# ioboard2.net
KiCad netlist of a schematic drawn in EAGLE
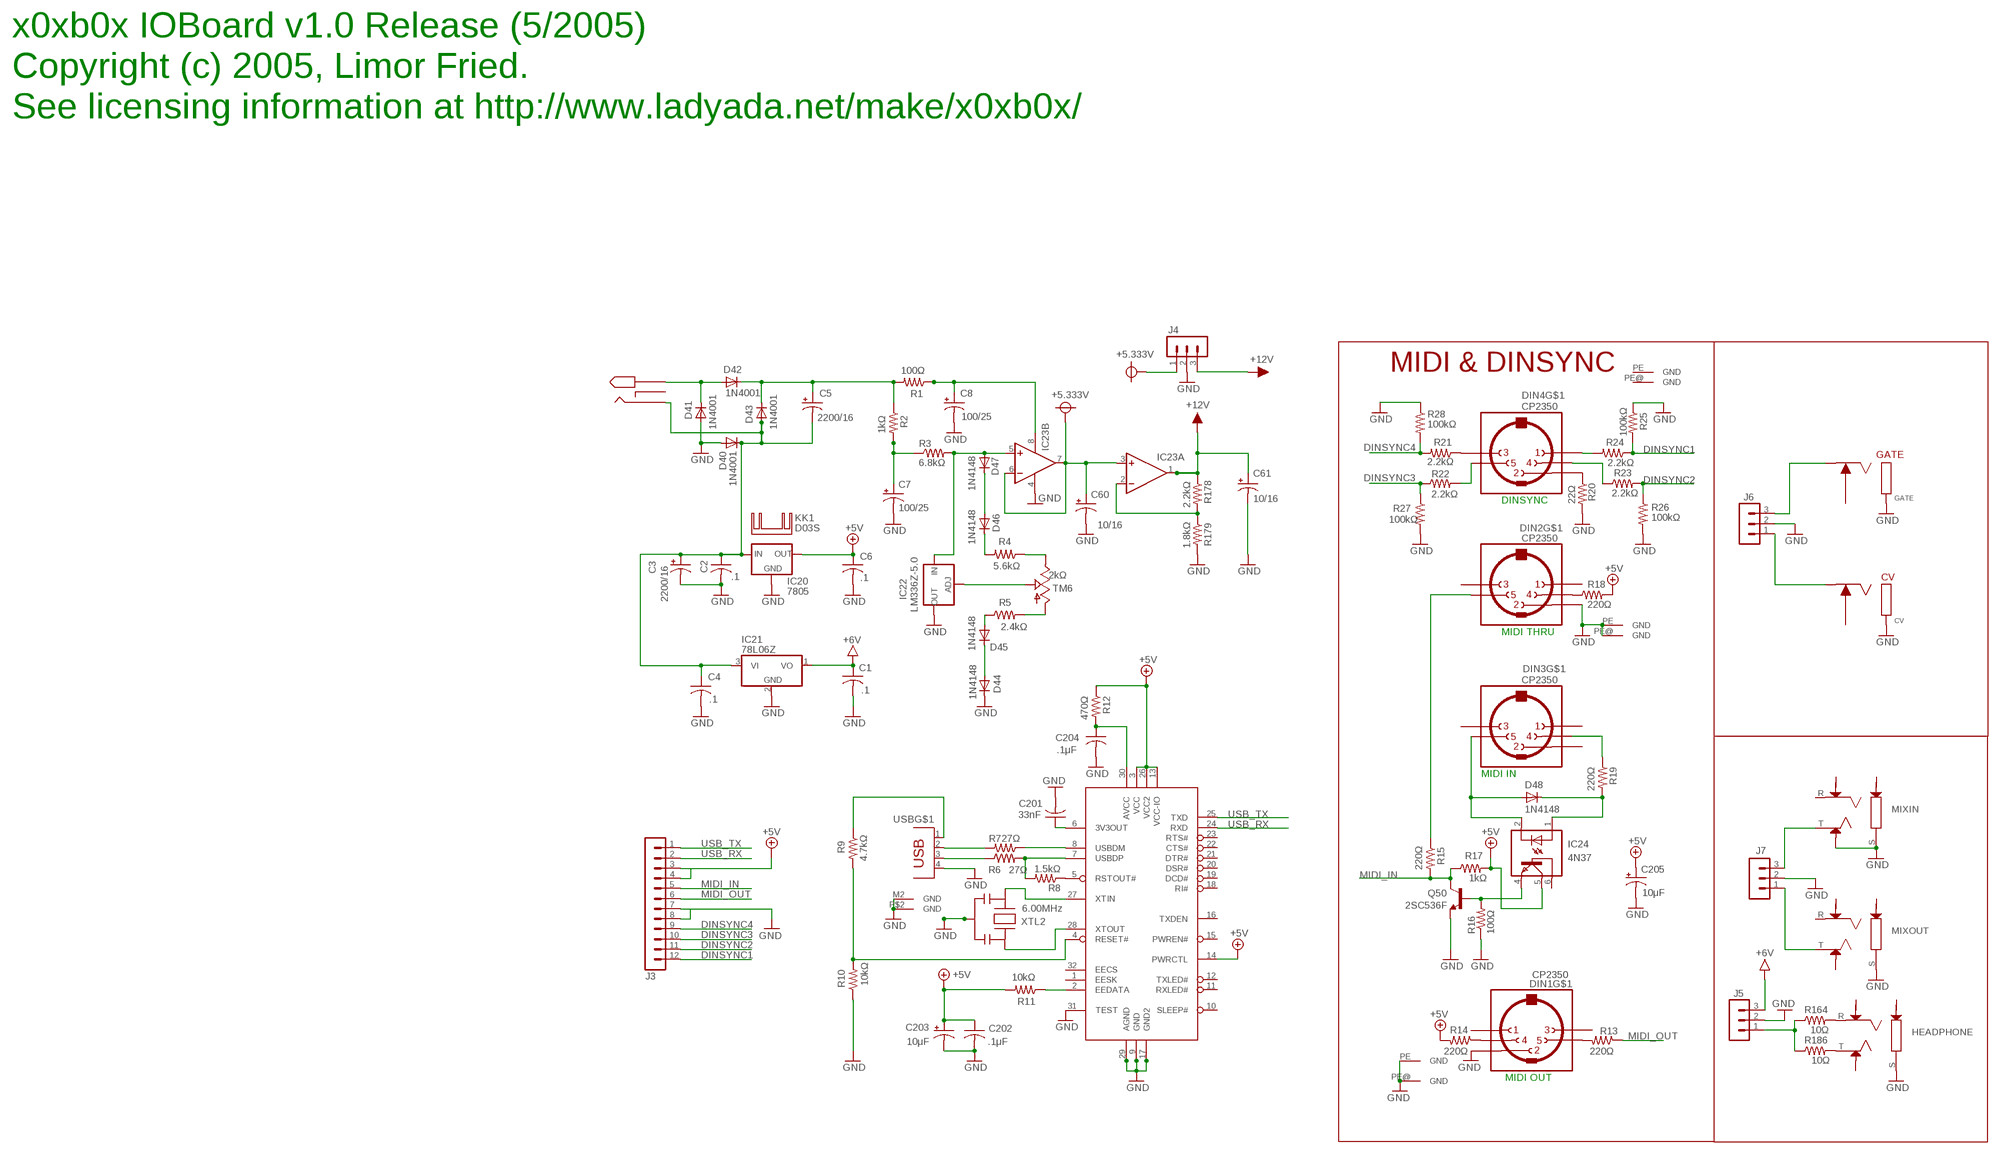
[diagram p0: schematic, sheet 1]

(export (version "E")
  (design (tool "Eeschema 10.0.6"))
  (components
    (comp (ref "C1")
      (value ".1")
      (footprint "eagle-import:C050H075X075")
      (libsource (lib "eagle-import") (part "C-US050H075X075"))
    )
    (comp (ref "C2")
      (value ".1")
      (footprint "eagle-import:C050H075X075")
      (libsource (lib "eagle-import") (part "C-US050H075X075"))
    )
    (comp (ref "C3")
      (value "2200/16")
      (footprint "eagle-import:E5-13")
      (libsource (lib "eagle-import") (part "CPOL-USE5-13"))
    )
    (comp (ref "C4")
      (value ".1")
      (footprint "eagle-import:C050H075X075")
      (libsource (lib "eagle-import") (part "C-US050H075X075"))
    )
    (comp (ref "C5")
      (value "2200/16")
      (footprint "eagle-import:E5-13")
      (libsource (lib "eagle-import") (part "CPOL-USE5-13"))
    )
    (comp (ref "C6")
      (value ".1")
      (footprint "eagle-import:C050H075X075")
      (libsource (lib "eagle-import") (part "C-US050H075X075"))
    )
    (comp (ref "C7")
      (value "100/25")
      (footprint "eagle-import:E5-6")
      (libsource (lib "eagle-import") (part "CPOL-USE5-6"))
    )
    (comp (ref "C8")
      (value "100/25")
      (footprint "eagle-import:E5-6")
      (libsource (lib "eagle-import") (part "CPOL-USE5-6"))
    )
    (comp (ref "C60")
      (value "10/16")
      (footprint "eagle-import:E5-6")
      (libsource (lib "eagle-import") (part "CPOL-USE5-6"))
    )
    (comp (ref "C61")
      (value "10/16")
      (footprint "eagle-import:E5-6")
      (libsource (lib "eagle-import") (part "CPOL-USE5-6"))
    )
    (comp (ref "C201")
      (value "33nF")
      (footprint "eagle-import:C050-025X075")
      (libsource (lib "eagle-import") (part "C-US050-025X075"))
    )
    (comp (ref "C202")
      (value ".1μF")
      (footprint "eagle-import:C050H075X075")
      (libsource (lib "eagle-import") (part "C-US050H075X075"))
    )
    (comp (ref "C203")
      (value "10μF")
      (footprint "eagle-import:E5-6")
      (libsource (lib "eagle-import") (part "CPOL-USE5-6"))
    )
    (comp (ref "C204")
      (value ".1μF")
      (footprint "eagle-import:C050H075X075")
      (libsource (lib "eagle-import") (part "C-US050H075X075"))
    )
    (comp (ref "C205")
      (value "10μF")
      (footprint "eagle-import:E5-6")
      (libsource (lib "eagle-import") (part "CPOL-USE5-6"))
    )
    (comp (ref "CV")
      (value "MONO_CC")
      (footprint "eagle-import:CP-3502")
      (libsource (lib "eagle-import") (part "MONO_CC"))
    )
    (comp (ref "D40")
      (value "1N4001")
      (footprint "eagle-import:DO41-10")
      (libsource (lib "eagle-import") (part "1N4004"))
    )
    (comp (ref "D41")
      (value "1N4001")
      (footprint "eagle-import:DO41-10")
      (libsource (lib "eagle-import") (part "1N4004"))
    )
    (comp (ref "D42")
      (value "1N4001")
      (footprint "eagle-import:DO41-10")
      (libsource (lib "eagle-import") (part "1N4004"))
    )
    (comp (ref "D43")
      (value "1N4001")
      (footprint "eagle-import:DO41-10")
      (libsource (lib "eagle-import") (part "1N4004"))
    )
    (comp (ref "D44")
      (value "1N4148")
      (footprint "eagle-import:DO35-10")
      (libsource (lib "eagle-import") (part "1N4148"))
    )
    (comp (ref "D45")
      (value "1N4148")
      (footprint "eagle-import:DO35-10")
      (libsource (lib "eagle-import") (part "1N4148"))
    )
    (comp (ref "D46")
      (value "1N4148")
      (footprint "eagle-import:DO35-10")
      (libsource (lib "eagle-import") (part "1N4148"))
    )
    (comp (ref "D47")
      (value "1N4148")
      (footprint "eagle-import:DO35-10")
      (libsource (lib "eagle-import") (part "1N4148"))
    )
    (comp (ref "D48")
      (value "1N4148")
      (footprint "eagle-import:DO35-10")
      (libsource (lib "eagle-import") (part "1N4148"))
    )
    (comp (ref "DIN1")
      (value "CP2350")
      (footprint "eagle-import:CP-2350")
      (libsource (lib "eagle-import") (part "CP2350"))
    )
    (comp (ref "DIN2")
      (value "CP2350")
      (footprint "eagle-import:CP-2350")
      (libsource (lib "eagle-import") (part "CP2350"))
    )
    (comp (ref "DIN3")
      (value "CP2350")
      (footprint "eagle-import:CP-2350")
      (libsource (lib "eagle-import") (part "CP2350"))
    )
    (comp (ref "DIN4")
      (value "CP2350")
      (footprint "eagle-import:CP-2350")
      (libsource (lib "eagle-import") (part "CP2350"))
    )
    (comp (ref "GATE")
      (value "MONO_CC")
      (footprint "eagle-import:CP-3502")
      (libsource (lib "eagle-import") (part "MONO_CC"))
    )
    (comp (ref "HEADPHONE")
      (value "NEUTRIX_STEREO")
      (footprint "eagle-import:REAN_1_4STERO")
      (libsource (lib "eagle-import") (part "NEUTRIX_STEREO"))
    )
    (comp (ref "IC20")
      (value "7805")
      (footprint "eagle-import:78XXS")
      (libsource (lib "eagle-import") (part "78XXS"))
    )
    (comp (ref "IC21")
      (value "78L06Z")
      (footprint "eagle-import:TO92")
      (libsource (lib "eagle-import") (part "78ZL05"))
    )
    (comp (ref "IC22")
      (value "LM336Z-5.0")
      (footprint "eagle-import:2SC536F")
      (libsource (lib "eagle-import") (part "LM337LX0X"))
    )
    (comp (ref "IC23")
      (value "AN6562N")
      (footprint "eagle-import:DIL08")
      (libsource (lib "eagle-import") (part "AN6562N"))
    )
    (comp (ref "IC24")
      (value "4N37")
      (footprint "eagle-import:DIL06")
      (libsource (lib "eagle-import") (part "4N37"))
    )
    (comp (ref "IC25")
      (value "FT232")
      (footprint "eagle-import:SQFP-S-7X7-32")
      (libsource (lib "eagle-import") (part "FT232"))
    )
    (comp (ref "J3")
      (value "MA12-1")
      (footprint "eagle-import:MA12-1")
      (libsource (lib "eagle-import") (part "MA12-1"))
    )
    (comp (ref "J4")
      (value "MA03-1")
      (footprint "eagle-import:MA03-1")
      (libsource (lib "eagle-import") (part "MA03-1"))
    )
    (comp (ref "J5")
      (value "MA03-1")
      (footprint "eagle-import:MA03-1")
      (libsource (lib "eagle-import") (part "MA03-1"))
    )
    (comp (ref "J6")
      (value "MA03-1")
      (footprint "eagle-import:MA03-1")
      (libsource (lib "eagle-import") (part "MA03-1"))
    )
    (comp (ref "J7")
      (value "MA03-1")
      (footprint "eagle-import:MA03-1")
      (libsource (lib "eagle-import") (part "MA03-1"))
    )
    (comp (ref "KK1")
      (value "D03S")
      (footprint "eagle-import:D03S")
      (libsource (lib "eagle-import") (part "D03S"))
    )
    (comp (ref "MIXIN")
      (value "NEUTRIX_STEREO")
      (footprint "eagle-import:REAN_1_4STERO")
      (libsource (lib "eagle-import") (part "NEUTRIX_STEREO"))
    )
    (comp (ref "MIXOUT")
      (value "NEUTRIX_STEREO")
      (footprint "eagle-import:REAN_1_4STERO")
      (libsource (lib "eagle-import") (part "NEUTRIX_STEREO"))
    )
    (comp (ref "POWER")
      (value "2.1MMJACK")
      (footprint "eagle-import:PJ-102A")
      (libsource (lib "eagle-import") (part "2.1MMJACK"))
    )
    (comp (ref "Q50")
      (value "2SC536F")
      (footprint "eagle-import:2SC536F")
      (libsource (lib "eagle-import") (part "2SC536F"))
    )
    (comp (ref "R1")
      (value "100Ω")
      (footprint "eagle-import:0207_5V")
      (libsource (lib "eagle-import") (part "R-US_0207/5V"))
    )
    (comp (ref "R2")
      (value "1kΩ")
      (footprint "eagle-import:0207_5V")
      (libsource (lib "eagle-import") (part "R-US_0207/5V"))
    )
    (comp (ref "R3")
      (value "6.8kΩ")
      (footprint "eagle-import:0207_5V")
      (libsource (lib "eagle-import") (part "R-US_0207/5V"))
    )
    (comp (ref "R4")
      (value "5.6kΩ")
      (footprint "eagle-import:0207_5V")
      (libsource (lib "eagle-import") (part "R-US_0207/5V"))
    )
    (comp (ref "R5")
      (value "2.4kΩ")
      (footprint "eagle-import:0207_5V")
      (libsource (lib "eagle-import") (part "R-US_0207/5V"))
    )
    (comp (ref "R6")
      (value "27Ω")
      (footprint "eagle-import:0207_5V")
      (libsource (lib "eagle-import") (part "R-US_0207/5V"))
    )
    (comp (ref "R7")
      (value "27Ω")
      (footprint "eagle-import:0207_5V")
      (libsource (lib "eagle-import") (part "R-US_0207/5V"))
    )
    (comp (ref "R8")
      (value "1.5kΩ")
      (footprint "eagle-import:0207_5V")
      (libsource (lib "eagle-import") (part "R-US_0207/5V"))
    )
    (comp (ref "R9")
      (value "4.7kΩ")
      (footprint "eagle-import:0207_5V")
      (libsource (lib "eagle-import") (part "R-US_0207/5V"))
    )
    (comp (ref "R10")
      (value "10kΩ")
      (footprint "eagle-import:0207_5V")
      (libsource (lib "eagle-import") (part "R-US_0207/5V"))
    )
    (comp (ref "R11")
      (value "10kΩ")
      (footprint "eagle-import:0207_5V")
      (libsource (lib "eagle-import") (part "R-US_0207/5V"))
    )
    (comp (ref "R12")
      (value "470Ω")
      (footprint "eagle-import:0207_5V")
      (libsource (lib "eagle-import") (part "R-US_0207/5V"))
    )
    (comp (ref "R13")
      (value "220Ω")
      (footprint "eagle-import:0207_5V")
      (libsource (lib "eagle-import") (part "R-US_0207/5V"))
    )
    (comp (ref "R14")
      (value "220Ω")
      (footprint "eagle-import:0207_5V")
      (libsource (lib "eagle-import") (part "R-US_0207/5V"))
    )
    (comp (ref "R15")
      (value "220Ω")
      (footprint "eagle-import:0207_5V")
      (libsource (lib "eagle-import") (part "R-US_0207/5V"))
    )
    (comp (ref "R16")
      (value "100Ω")
      (footprint "eagle-import:0207_5V")
      (libsource (lib "eagle-import") (part "R-US_0207/5V"))
    )
    (comp (ref "R17")
      (value "1kΩ")
      (footprint "eagle-import:0207_5V")
      (libsource (lib "eagle-import") (part "R-US_0207/5V"))
    )
    (comp (ref "R18")
      (value "220Ω")
      (footprint "eagle-import:0207_5V")
      (libsource (lib "eagle-import") (part "R-US_0207/5V"))
    )
    (comp (ref "R19")
      (value "220Ω")
      (footprint "eagle-import:0207_5V")
      (libsource (lib "eagle-import") (part "R-US_0207/5V"))
    )
    (comp (ref "R20")
      (value "22Ω")
      (footprint "eagle-import:0207_5V")
      (libsource (lib "eagle-import") (part "R-US_0207/5V"))
    )
    (comp (ref "R21")
      (value "2.2kΩ")
      (footprint "eagle-import:0207_5V")
      (libsource (lib "eagle-import") (part "R-US_0207/5V"))
    )
    (comp (ref "R22")
      (value "2.2kΩ")
      (footprint "eagle-import:0207_5V")
      (libsource (lib "eagle-import") (part "R-US_0207/5V"))
    )
    (comp (ref "R23")
      (value "2.2kΩ")
      (footprint "eagle-import:0207_5V")
      (libsource (lib "eagle-import") (part "R-US_0207/5V"))
    )
    (comp (ref "R24")
      (value "2.2kΩ")
      (footprint "eagle-import:0207_5V")
      (libsource (lib "eagle-import") (part "R-US_0207/5V"))
    )
    (comp (ref "R25")
      (value "100kΩ")
      (footprint "eagle-import:0207_5V")
      (libsource (lib "eagle-import") (part "R-US_0207/5V"))
    )
    (comp (ref "R26")
      (value "100kΩ")
      (footprint "eagle-import:0207_5V")
      (libsource (lib "eagle-import") (part "R-US_0207/5V"))
    )
    (comp (ref "R27")
      (value "100kΩ")
      (footprint "eagle-import:0207_5V")
      (libsource (lib "eagle-import") (part "R-US_0207/5V"))
    )
    (comp (ref "R28")
      (value "100kΩ")
      (footprint "eagle-import:0207_5V")
      (libsource (lib "eagle-import") (part "R-US_0207/5V"))
    )
    (comp (ref "R164")
      (value "10Ω")
      (footprint "eagle-import:0207_5V")
      (libsource (lib "eagle-import") (part "R-US_0207/5V"))
    )
    (comp (ref "R178")
      (value "2.2kΩ")
      (footprint "eagle-import:0207_5V")
      (libsource (lib "eagle-import") (part "R-US_0207/5V"))
    )
    (comp (ref "R179")
      (value "1.8kΩ")
      (footprint "eagle-import:0207_5V")
      (libsource (lib "eagle-import") (part "R-US_0207/5V"))
    )
    (comp (ref "R186")
      (value "10Ω")
      (footprint "eagle-import:0207_5V")
      (libsource (lib "eagle-import") (part "R-US_0207/5V"))
    )
    (comp (ref "TM6")
      (value "2kΩ")
      (footprint "eagle-import:306")
      (libsource (lib "eagle-import") (part "TRIM_US-"))
    )
    (comp (ref "USB")
      (value "ACON_TYPEB")
      (footprint "eagle-import:PN61729")
      (libsource (lib "eagle-import") (part "ACON_TYPEB"))
    )
    (comp (ref "XTL2")
      (value "6.00MHz")
      (footprint "eagle-import:ZTT_XTAL")
      (libsource (lib "eagle-import") (part "ZTT"))
    )
  )
  (nets
    (net (code "1") (name "+5.333V") (class "Default")
      (node (ref "C60") (pin "+") (pinfunction "+_+") (pintype "passive"))
      (node (ref "IC23") (pin "3") (pinfunction "+IN_3") (pintype "input"))
      (node (ref "IC23") (pin "6") (pinfunction "-IN_6") (pintype "input"))
      (node (ref "IC23") (pin "7") (pinfunction "OUT_7") (pintype "output"))
      (node (ref "J4") (pin "1") (pinfunction "1_1") (pintype "passive"))
    )
    (net (code "2") (name "+5V") (class "Default")
      (node (ref "C202") (pin "1") (pinfunction "1_1") (pintype "passive"))
      (node (ref "C203") (pin "+") (pinfunction "+_+") (pintype "passive"))
      (node (ref "C205") (pin "+") (pinfunction "+_+") (pintype "passive"))
      (node (ref "C6") (pin "1") (pinfunction "1_1") (pintype "passive"))
      (node (ref "IC20") (pin "OUT") (pinfunction "OUT_OUT") (pintype "passive"))
      (node (ref "IC24") (pin "5") (pinfunction "COL_5") (pintype "passive"))
      (node (ref "IC25") (pin "13") (pinfunction "VCC-IO_13") (pintype "bidirectional"))
      (node (ref "IC25") (pin "14") (pinfunction "PWRCTL_14") (pintype "bidirectional"))
      (node (ref "IC25") (pin "26") (pinfunction "VCC2_26") (pintype "bidirectional"))
      (node (ref "IC25") (pin "3") (pinfunction "VCC_3") (pintype "bidirectional"))
      (node (ref "J3") (pin "3") (pinfunction "3_3") (pintype "passive"))
      (node (ref "J3") (pin "4") (pinfunction "4_4") (pintype "passive"))
      (node (ref "R11") (pin "2") (pinfunction "2_2") (pintype "passive"))
      (node (ref "R12") (pin "1") (pinfunction "1_1") (pintype "passive"))
      (node (ref "R14") (pin "2") (pinfunction "2_2") (pintype "passive"))
      (node (ref "R17") (pin "2") (pinfunction "2_2") (pintype "passive"))
      (node (ref "R18") (pin "2") (pinfunction "2_2") (pintype "passive"))
    )
    (net (code "3") (name "+6V") (class "Default")
      (node (ref "C1") (pin "1") (pinfunction "1_1") (pintype "passive"))
      (node (ref "IC21") (pin "1") (pinfunction "VO_1") (pintype "passive"))
      (node (ref "J5") (pin "3") (pinfunction "3_3") (pintype "passive"))
    )
    (net (code "4") (name "+12V") (class "Default")
      (node (ref "C61") (pin "+") (pinfunction "+_+") (pintype "passive"))
      (node (ref "IC23") (pin "1") (pinfunction "OUT_1") (pintype "output"))
      (node (ref "J4") (pin "3") (pinfunction "3_3") (pintype "passive"))
      (node (ref "R178") (pin "1") (pinfunction "1_1") (pintype "passive"))
    )
    (net (code "5") (name "/DINSYNC1") (class "Default")
      (node (ref "J3") (pin "12") (pinfunction "12_12") (pintype "passive"))
      (node (ref "R24") (pin "1") (pinfunction "1_1") (pintype "passive"))
      (node (ref "R25") (pin "2") (pinfunction "2_2") (pintype "passive"))
    )
    (net (code "6") (name "/DINSYNC2") (class "Default")
      (node (ref "J3") (pin "11") (pinfunction "11_11") (pintype "passive"))
      (node (ref "R23") (pin "2") (pinfunction "2_2") (pintype "passive"))
      (node (ref "R26") (pin "1") (pinfunction "1_1") (pintype "passive"))
    )
    (net (code "7") (name "/DINSYNC3") (class "Default")
      (node (ref "J3") (pin "10") (pinfunction "10_10") (pintype "passive"))
      (node (ref "R22") (pin "1") (pinfunction "1_1") (pintype "passive"))
      (node (ref "R27") (pin "1") (pinfunction "1_1") (pintype "passive"))
    )
    (net (code "8") (name "/DINSYNC4") (class "Default")
      (node (ref "J3") (pin "9") (pinfunction "9_9") (pintype "passive"))
      (node (ref "R21") (pin "2") (pinfunction "2_2") (pintype "passive"))
      (node (ref "R28") (pin "2") (pinfunction "2_2") (pintype "passive"))
    )
    (net (code "9") (name "/MIDI_IN") (class "Default")
      (node (ref "J3") (pin "5") (pinfunction "5_5") (pintype "passive"))
      (node (ref "Q50") (pin "2") (pinfunction "C_2") (pintype "passive"))
      (node (ref "R15") (pin "2") (pinfunction "2_2") (pintype "passive"))
      (node (ref "R17") (pin "1") (pinfunction "1_1") (pintype "passive"))
    )
    (net (code "10") (name "/MIDI_OUT") (class "Default")
      (node (ref "J3") (pin "6") (pinfunction "6_6") (pintype "passive"))
      (node (ref "R13") (pin "1") (pinfunction "1_1") (pintype "passive"))
    )
    (net (code "11") (name "/USB_RX") (class "Default")
      (node (ref "IC25") (pin "24") (pinfunction "RXD_24") (pintype "bidirectional"))
      (node (ref "J3") (pin "2") (pinfunction "2_2") (pintype "passive"))
    )
    (net (code "12") (name "/USB_TX") (class "Default")
      (node (ref "IC25") (pin "25") (pinfunction "TXD_25") (pintype "bidirectional"))
      (node (ref "J3") (pin "1") (pinfunction "1_1") (pintype "passive"))
    )
    (net (code "13") (name "GND") (class "Default")
      (node (ref "C1") (pin "2") (pinfunction "2_2") (pintype "passive"))
      (node (ref "C2") (pin "2") (pinfunction "2_2") (pintype "passive"))
      (node (ref "C201") (pin "2") (pinfunction "2_2") (pintype "passive"))
      (node (ref "C202") (pin "2") (pinfunction "2_2") (pintype "passive"))
      (node (ref "C203") (pin "-") (pinfunction "-_-") (pintype "passive"))
      (node (ref "C204") (pin "2") (pinfunction "2_2") (pintype "passive"))
      (node (ref "C205") (pin "-") (pinfunction "-_-") (pintype "passive"))
      (node (ref "C3") (pin "-") (pinfunction "-_-") (pintype "passive"))
      (node (ref "C4") (pin "2") (pinfunction "2_2") (pintype "passive"))
      (node (ref "C6") (pin "2") (pinfunction "2_2") (pintype "passive"))
      (node (ref "C60") (pin "-") (pinfunction "-_-") (pintype "passive"))
      (node (ref "C61") (pin "-") (pinfunction "-_-") (pintype "passive"))
      (node (ref "C7") (pin "-") (pinfunction "-_-") (pintype "passive"))
      (node (ref "C8") (pin "-") (pinfunction "-_-") (pintype "passive"))
      (node (ref "CV") (pin "SLEEVE") (pinfunction "SLEEVE_SLEEVE") (pintype "input"))
      (node (ref "D40") (pin "A") (pinfunction "A_A") (pintype "passive"))
      (node (ref "D41") (pin "A") (pinfunction "A_A") (pintype "passive"))
      (node (ref "D44") (pin "C") (pinfunction "C_C") (pintype "passive"))
      (node (ref "DIN1") (pin "2") (pinfunction "2_2") (pintype "passive"))
      (node (ref "DIN1") (pin "PE") (pinfunction "GND_PE") (pintype "passive"))
      (node (ref "DIN1") (pin "PE@") (pinfunction "GND_PE@") (pintype "passive"))
      (node (ref "DIN2") (pin "2") (pinfunction "2_2") (pintype "passive"))
      (node (ref "DIN2") (pin "PE") (pinfunction "GND_PE") (pintype "passive"))
      (node (ref "DIN2") (pin "PE@") (pinfunction "GND_PE@") (pintype "passive"))
      (node (ref "GATE") (pin "SLEEVE") (pinfunction "SLEEVE_SLEEVE") (pintype "input"))
      (node (ref "HEADPHONE") (pin "S") (pinfunction "S_S") (pintype "input"))
      (node (ref "IC20") (pin "GND") (pinfunction "GND_GND") (pintype "input"))
      (node (ref "IC21") (pin "2") (pinfunction "GND_2") (pintype "passive"))
      (node (ref "IC22") (pin "3") (pinfunction "OUT_3") (pintype "passive"))
      (node (ref "IC23") (pin "4") (pinfunction "V-_4") (pintype "power_in"))
      (node (ref "IC25") (pin "17") (pinfunction "GND2_17") (pintype "bidirectional"))
      (node (ref "IC25") (pin "29") (pinfunction "AGND_29") (pintype "bidirectional"))
      (node (ref "IC25") (pin "31") (pinfunction "TEST_31") (pintype "bidirectional"))
      (node (ref "IC25") (pin "9") (pinfunction "GND_9") (pintype "bidirectional"))
      (node (ref "J3") (pin "7") (pinfunction "7_7") (pintype "passive"))
      (node (ref "J3") (pin "8") (pinfunction "8_8") (pintype "passive"))
      (node (ref "J4") (pin "2") (pinfunction "2_2") (pintype "passive"))
      (node (ref "J5") (pin "2") (pinfunction "2_2") (pintype "passive"))
      (node (ref "J6") (pin "2") (pinfunction "2_2") (pintype "passive"))
      (node (ref "J7") (pin "2") (pinfunction "2_2") (pintype "passive"))
      (node (ref "MIXIN") (pin "S") (pinfunction "S_S") (pintype "input"))
      (node (ref "MIXIN") (pin "TN") (pinfunction "TN_TN") (pintype "passive"))
      (node (ref "MIXOUT") (pin "S") (pinfunction "S_S") (pintype "input"))
      (node (ref "Q50") (pin "3") (pinfunction "E_3") (pintype "passive"))
      (node (ref "R10") (pin "1") (pinfunction "1_1") (pintype "passive"))
      (node (ref "R16") (pin "1") (pinfunction "1_1") (pintype "passive"))
      (node (ref "R179") (pin "2") (pinfunction "2_2") (pintype "passive"))
      (node (ref "R20") (pin "2") (pinfunction "2_2") (pintype "passive"))
      (node (ref "R25") (pin "1") (pinfunction "1_1") (pintype "passive"))
      (node (ref "R26") (pin "2") (pinfunction "2_2") (pintype "passive"))
      (node (ref "R27") (pin "2") (pinfunction "2_2") (pintype "passive"))
      (node (ref "R28") (pin "1") (pinfunction "1_1") (pintype "passive"))
      (node (ref "USB") (pin "4") (pinfunction "4_4") (pintype "bidirectional"))
      (node (ref "USB") (pin "M2") (pinfunction "GND_M2") (pintype "passive"))
      (node (ref "USB") (pin "P$2") (pinfunction "GND_P$2") (pintype "passive"))
      (node (ref "XTL2") (pin "P$2") (pinfunction "GND_P$2") (pintype "bidirectional"))
    )
    (net (code "14") (name "Net-(C5-Pad+)") (class "Default")
      (node (ref "C5") (pin "+") (pinfunction "+_+") (pintype "passive"))
      (node (ref "D42") (pin "C") (pinfunction "C_C") (pintype "passive"))
      (node (ref "D43") (pin "C") (pinfunction "C_C") (pintype "passive"))
      (node (ref "R1") (pin "2") (pinfunction "2_2") (pintype "passive"))
      (node (ref "R2") (pin "1") (pinfunction "1_1") (pintype "passive"))
    )
    (net (code "15") (name "Net-(C7-Pad+)") (class "Default")
      (node (ref "C7") (pin "+") (pinfunction "+_+") (pintype "passive"))
      (node (ref "R2") (pin "2") (pinfunction "2_2") (pintype "passive"))
      (node (ref "R3") (pin "1") (pinfunction "1_1") (pintype "passive"))
    )
    (net (code "16") (name "Net-(CV-PadTIP)") (class "Default")
      (node (ref "CV") (pin "TIP") (pinfunction "TIP_TIP") (pintype "input"))
      (node (ref "J6") (pin "1") (pinfunction "1_1") (pintype "passive"))
    )
    (net (code "17") (name "Net-(D41-PadC)") (class "Default")
      (node (ref "D41") (pin "C") (pinfunction "C_C") (pintype "passive"))
      (node (ref "D42") (pin "A") (pinfunction "A_A") (pintype "passive"))
      (node (ref "POWER") (pin "P$1") (pinfunction "P$1_P$1") (pintype "bidirectional"))
    )
    (net (code "18") (name "Net-(D44-PadA)") (class "Default")
      (node (ref "D44") (pin "A") (pinfunction "A_A") (pintype "passive"))
      (node (ref "D45") (pin "C") (pinfunction "C_C") (pintype "passive"))
    )
    (net (code "19") (name "Net-(D45-PadA)") (class "Default")
      (node (ref "D45") (pin "A") (pinfunction "A_A") (pintype "passive"))
      (node (ref "R5") (pin "1") (pinfunction "1_1") (pintype "passive"))
    )
    (net (code "20") (name "Net-(D46-PadA)") (class "Default")
      (node (ref "D46") (pin "A") (pinfunction "A_A") (pintype "passive"))
      (node (ref "D47") (pin "C") (pinfunction "C_C") (pintype "passive"))
    )
    (net (code "21") (name "Net-(D46-PadC)") (class "Default")
      (node (ref "D46") (pin "C") (pinfunction "C_C") (pintype "passive"))
      (node (ref "R4") (pin "2") (pinfunction "2_2") (pintype "passive"))
    )
    (net (code "22") (name "Net-(DIN1-Pad4)") (class "Default")
      (node (ref "DIN1") (pin "4") (pinfunction "4_4") (pintype "passive"))
      (node (ref "R14") (pin "1") (pinfunction "1_1") (pintype "passive"))
    )
    (net (code "23") (name "Net-(DIN1-Pad5)") (class "Default")
      (node (ref "DIN1") (pin "5") (pinfunction "5_5") (pintype "passive"))
      (node (ref "R13") (pin "2") (pinfunction "2_2") (pintype "passive"))
    )
    (net (code "24") (name "Net-(DIN2-Pad4)") (class "Default")
      (node (ref "DIN2") (pin "4") (pinfunction "4_4") (pintype "passive"))
      (node (ref "R18") (pin "1") (pinfunction "1_1") (pintype "passive"))
    )
    (net (code "25") (name "Net-(DIN2-Pad5)") (class "Default")
      (node (ref "DIN2") (pin "5") (pinfunction "5_5") (pintype "passive"))
      (node (ref "R15") (pin "1") (pinfunction "1_1") (pintype "passive"))
    )
    (net (code "26") (name "Net-(DIN3-Pad4)") (class "Default")
      (node (ref "DIN3") (pin "4") (pinfunction "4_4") (pintype "passive"))
      (node (ref "R19") (pin "1") (pinfunction "1_1") (pintype "passive"))
    )
    (net (code "27") (name "Net-(DIN4-Pad1)") (class "Default")
      (node (ref "DIN4") (pin "1") (pinfunction "1_1") (pintype "passive"))
      (node (ref "R24") (pin "2") (pinfunction "2_2") (pintype "passive"))
    )
    (net (code "28") (name "Net-(DIN4-Pad2)") (class "Default")
      (node (ref "DIN4") (pin "2") (pinfunction "2_2") (pintype "passive"))
      (node (ref "R20") (pin "1") (pinfunction "1_1") (pintype "passive"))
    )
    (net (code "29") (name "Net-(DIN4-Pad3)") (class "Default")
      (node (ref "DIN4") (pin "3") (pinfunction "3_3") (pintype "passive"))
      (node (ref "R21") (pin "1") (pinfunction "1_1") (pintype "passive"))
    )
    (net (code "30") (name "Net-(DIN4-Pad4)") (class "Default")
      (node (ref "DIN4") (pin "4") (pinfunction "4_4") (pintype "passive"))
      (node (ref "R23") (pin "1") (pinfunction "1_1") (pintype "passive"))
    )
    (net (code "31") (name "Net-(DIN4-Pad5)") (class "Default")
      (node (ref "DIN4") (pin "5") (pinfunction "5_5") (pintype "passive"))
      (node (ref "R22") (pin "2") (pinfunction "2_2") (pintype "passive"))
    )
    (net (code "32") (name "Net-(GATE-PadTIP)") (class "Default")
      (node (ref "GATE") (pin "TIP") (pinfunction "TIP_TIP") (pintype "input"))
      (node (ref "J6") (pin "3") (pinfunction "3_3") (pintype "passive"))
    )
    (net (code "33") (name "Net-(HEADPHONE-PadR)") (class "Default")
      (node (ref "HEADPHONE") (pin "R") (pinfunction "R_R") (pintype "input"))
      (node (ref "R164") (pin "2") (pinfunction "2_2") (pintype "passive"))
    )
    (net (code "34") (name "Net-(HEADPHONE-PadT)") (class "Default")
      (node (ref "HEADPHONE") (pin "T") (pinfunction "T_T") (pintype "input"))
      (node (ref "R186") (pin "2") (pinfunction "2_2") (pintype "passive"))
    )
    (net (code "35") (name "Net-(IC21-VI)") (class "Default")
      (node (ref "C2") (pin "1") (pinfunction "1_1") (pintype "passive"))
      (node (ref "C3") (pin "+") (pinfunction "+_+") (pintype "passive"))
      (node (ref "C4") (pin "1") (pinfunction "1_1") (pintype "passive"))
      (node (ref "C5") (pin "-") (pinfunction "-_-") (pintype "passive"))
      (node (ref "D40") (pin "C") (pinfunction "C_C") (pintype "passive"))
      (node (ref "D43") (pin "A") (pinfunction "A_A") (pintype "passive"))
      (node (ref "IC20") (pin "IN") (pinfunction "IN_IN") (pintype "input"))
      (node (ref "IC21") (pin "3") (pinfunction "VI_3") (pintype "input"))
      (node (ref "POWER") (pin "P$2") (pinfunction "P$2_P$2") (pintype "bidirectional"))
    )
    (net (code "36") (name "Net-(IC22-ADJ)") (class "Default")
      (node (ref "IC22") (pin "1") (pinfunction "ADJ_1") (pintype "input"))
      (node (ref "TM6") (pin "2") (pinfunction "S_2") (pintype "passive"))
    )
    (net (code "37") (name "Net-(IC22-IN)") (class "Default")
      (node (ref "D47") (pin "A") (pinfunction "A_A") (pintype "passive"))
      (node (ref "IC22") (pin "2") (pinfunction "IN_2") (pintype "input"))
      (node (ref "IC23") (pin "5") (pinfunction "+IN_5") (pintype "input"))
      (node (ref "R3") (pin "2") (pinfunction "2_2") (pintype "passive"))
    )
    (net (code "38") (name "Net-(IC23A--IN)") (class "Default")
      (node (ref "IC23") (pin "2") (pinfunction "-IN_2") (pintype "input"))
      (node (ref "R178") (pin "2") (pinfunction "2_2") (pintype "passive"))
      (node (ref "R179") (pin "1") (pinfunction "1_1") (pintype "passive"))
    )
    (net (code "39") (name "Net-(IC23C-V+)") (class "Default")
      (node (ref "C8") (pin "+") (pinfunction "+_+") (pintype "passive"))
      (node (ref "IC23") (pin "8") (pinfunction "V+_8") (pintype "power_in"))
      (node (ref "R1") (pin "1") (pinfunction "1_1") (pintype "passive"))
    )
    (net (code "40") (name "Net-(IC24-A)") (class "Default")
      (node (ref "D48") (pin "C") (pinfunction "C_C") (pintype "passive"))
      (node (ref "IC24") (pin "1") (pinfunction "A_1") (pintype "passive"))
      (node (ref "R19") (pin "2") (pinfunction "2_2") (pintype "passive"))
    )
    (net (code "41") (name "Net-(IC24-C)") (class "Default")
      (node (ref "D48") (pin "A") (pinfunction "A_A") (pintype "passive"))
      (node (ref "DIN3") (pin "5") (pinfunction "5_5") (pintype "passive"))
      (node (ref "IC24") (pin "2") (pinfunction "C_2") (pintype "passive"))
    )
    (net (code "42") (name "Net-(IC24-EMI)") (class "Default")
      (node (ref "IC24") (pin "4") (pinfunction "EMI_4") (pintype "passive"))
      (node (ref "Q50") (pin "1") (pinfunction "B_1") (pintype "passive"))
      (node (ref "R16") (pin "2") (pinfunction "2_2") (pintype "passive"))
    )
    (net (code "43") (name "Net-(IC25-3V3OUT)") (class "Default")
      (node (ref "C201") (pin "1") (pinfunction "1_1") (pintype "passive"))
      (node (ref "IC25") (pin "6") (pinfunction "3V3OUT_6") (pintype "bidirectional"))
    )
    (net (code "44") (name "Net-(IC25-AVCC)") (class "Default")
      (node (ref "C204") (pin "1") (pinfunction "1_1") (pintype "passive"))
      (node (ref "IC25") (pin "30") (pinfunction "AVCC_30") (pintype "bidirectional"))
      (node (ref "R12") (pin "2") (pinfunction "2_2") (pintype "passive"))
    )
    (net (code "45") (name "Net-(IC25-EEDATA)") (class "Default")
      (node (ref "IC25") (pin "2") (pinfunction "EEDATA_2") (pintype "bidirectional"))
      (node (ref "R11") (pin "1") (pinfunction "1_1") (pintype "passive"))
    )
    (net (code "46") (name "Net-(IC25-RESET#)") (class "Default")
      (node (ref "IC25") (pin "4") (pinfunction "RESET#_4") (pintype "bidirectional"))
      (node (ref "R10") (pin "2") (pinfunction "2_2") (pintype "passive"))
      (node (ref "R9") (pin "2") (pinfunction "2_2") (pintype "passive"))
    )
    (net (code "47") (name "Net-(IC25-RSTOUT#)") (class "Default")
      (node (ref "IC25") (pin "5") (pinfunction "RSTOUT#_5") (pintype "bidirectional"))
      (node (ref "R8") (pin "1") (pinfunction "1_1") (pintype "passive"))
    )
    (net (code "48") (name "Net-(IC25-USBDM)") (class "Default")
      (node (ref "IC25") (pin "8") (pinfunction "USBDM_8") (pintype "bidirectional"))
      (node (ref "R6") (pin "1") (pinfunction "1_1") (pintype "passive"))
    )
    (net (code "49") (name "Net-(IC25-USBDP)") (class "Default")
      (node (ref "IC25") (pin "7") (pinfunction "USBDP_7") (pintype "bidirectional"))
      (node (ref "R7") (pin "2") (pinfunction "2_2") (pintype "passive"))
      (node (ref "R8") (pin "2") (pinfunction "2_2") (pintype "passive"))
    )
    (net (code "50") (name "Net-(IC25-XTIN)") (class "Default")
      (node (ref "IC25") (pin "27") (pinfunction "XTIN_27") (pintype "bidirectional"))
      (node (ref "XTL2") (pin "P$1") (pinfunction "IN_P$1") (pintype "bidirectional"))
    )
    (net (code "51") (name "Net-(IC25-XTOUT)") (class "Default")
      (node (ref "IC25") (pin "28") (pinfunction "XTOUT_28") (pintype "bidirectional"))
      (node (ref "XTL2") (pin "P$3") (pinfunction "OUT_P$3") (pintype "bidirectional"))
    )
    (net (code "52") (name "Net-(J5-Pad1)") (class "Default")
      (node (ref "J5") (pin "1") (pinfunction "1_1") (pintype "passive"))
      (node (ref "R164") (pin "1") (pinfunction "1_1") (pintype "passive"))
      (node (ref "R186") (pin "1") (pinfunction "1_1") (pintype "passive"))
    )
    (net (code "53") (name "Net-(J7-Pad1)") (class "Default")
      (node (ref "J7") (pin "1") (pinfunction "1_1") (pintype "passive"))
      (node (ref "MIXOUT") (pin "T") (pinfunction "T_T") (pintype "input"))
    )
    (net (code "54") (name "Net-(J7-Pad3)") (class "Default")
      (node (ref "J7") (pin "3") (pinfunction "3_3") (pintype "passive"))
      (node (ref "MIXIN") (pin "T") (pinfunction "T_T") (pintype "input"))
    )
    (net (code "55") (name "Net-(R6-Pad2)") (class "Default")
      (node (ref "R6") (pin "2") (pinfunction "2_2") (pintype "passive"))
      (node (ref "USB") (pin "2") (pinfunction "2_2") (pintype "bidirectional"))
    )
    (net (code "56") (name "Net-(R7-Pad1)") (class "Default")
      (node (ref "R7") (pin "1") (pinfunction "1_1") (pintype "passive"))
      (node (ref "USB") (pin "3") (pinfunction "3_3") (pintype "bidirectional"))
    )
    (net (code "57") (name "Net-(R9-Pad1)") (class "Default")
      (node (ref "R9") (pin "1") (pinfunction "1_1") (pintype "passive"))
      (node (ref "USB") (pin "1") (pinfunction "1_1") (pintype "bidirectional"))
    )
    (net (code "58") (name "Net-(TM6-A)") (class "Default")
      (node (ref "R5") (pin "2") (pinfunction "2_2") (pintype "passive"))
      (node (ref "TM6") (pin "1") (pinfunction "A_1") (pintype "passive"))
    )
    (net (code "59") (name "Net-(TM6-E)") (class "Default")
      (node (ref "R4") (pin "1") (pinfunction "1_1") (pintype "passive"))
      (node (ref "TM6") (pin "3") (pinfunction "E_3") (pintype "passive"))
    )
    (net (code "60") (name "unconnected-(CV-PadTIPSHUNT)") (class "Default")
      (node (ref "CV") (pin "TIPSHUNT") (pinfunction "TIPSHUNT_TIPSHUNT") (pintype "input"))
    )
    (net (code "61") (name "unconnected-(DIN1-Pad1)") (class "Default")
      (node (ref "DIN1") (pin "1") (pinfunction "1_1") (pintype "passive"))
    )
    (net (code "62") (name "unconnected-(DIN1-Pad3)") (class "Default")
      (node (ref "DIN1") (pin "3") (pinfunction "3_3") (pintype "passive"))
    )
    (net (code "63") (name "unconnected-(DIN2-Pad1)") (class "Default")
      (node (ref "DIN2") (pin "1") (pinfunction "1_1") (pintype "passive"))
    )
    (net (code "64") (name "unconnected-(DIN2-Pad3)") (class "Default")
      (node (ref "DIN2") (pin "3") (pinfunction "3_3") (pintype "passive"))
    )
    (net (code "65") (name "unconnected-(DIN3-Pad1)") (class "Default")
      (node (ref "DIN3") (pin "1") (pinfunction "1_1") (pintype "passive"))
    )
    (net (code "66") (name "unconnected-(DIN3-Pad2)") (class "Default")
      (node (ref "DIN3") (pin "2") (pinfunction "2_2") (pintype "passive"))
    )
    (net (code "67") (name "unconnected-(DIN3-Pad3)") (class "Default")
      (node (ref "DIN3") (pin "3") (pinfunction "3_3") (pintype "passive"))
    )
    (net (code "68") (name "unconnected-(DIN4B-GND-PadPE)") (class "Default")
      (node (ref "DIN4") (pin "PE") (pinfunction "GND_PE") (pintype "passive"))
    )
    (net (code "69") (name "unconnected-(DIN4C-GND-PadPE@)") (class "Default")
      (node (ref "DIN4") (pin "PE@") (pinfunction "GND_PE@") (pintype "passive"))
    )
    (net (code "70") (name "unconnected-(GATE-PadTIPSHUNT)") (class "Default")
      (node (ref "GATE") (pin "TIPSHUNT") (pinfunction "TIPSHUNT_TIPSHUNT") (pintype "input"))
    )
    (net (code "71") (name "unconnected-(HEADPHONE-PadRN)") (class "Default")
      (node (ref "HEADPHONE") (pin "RN") (pinfunction "RN_RN") (pintype "passive"))
    )
    (net (code "72") (name "unconnected-(HEADPHONE-PadSN)") (class "Default")
      (node (ref "HEADPHONE") (pin "SN") (pinfunction "SN_SN") (pintype "passive"))
    )
    (net (code "73") (name "unconnected-(HEADPHONE-PadTN)") (class "Default")
      (node (ref "HEADPHONE") (pin "TN") (pinfunction "TN_TN") (pintype "passive"))
    )
    (net (code "74") (name "unconnected-(IC24-BAS-Pad6)") (class "Default")
      (node (ref "IC24") (pin "6") (pinfunction "BAS_6") (pintype "passive"))
    )
    (net (code "75") (name "unconnected-(IC25-CTS#-Pad22)") (class "Default")
      (node (ref "IC25") (pin "22") (pinfunction "CTS#_22") (pintype "bidirectional"))
    )
    (net (code "76") (name "unconnected-(IC25-DCD#-Pad19)") (class "Default")
      (node (ref "IC25") (pin "19") (pinfunction "DCD#_19") (pintype "bidirectional"))
    )
    (net (code "77") (name "unconnected-(IC25-DSR#-Pad20)") (class "Default")
      (node (ref "IC25") (pin "20") (pinfunction "DSR#_20") (pintype "bidirectional"))
    )
    (net (code "78") (name "unconnected-(IC25-DTR#-Pad21)") (class "Default")
      (node (ref "IC25") (pin "21") (pinfunction "DTR#_21") (pintype "bidirectional"))
    )
    (net (code "79") (name "unconnected-(IC25-EECS-Pad32)") (class "Default")
      (node (ref "IC25") (pin "32") (pinfunction "EECS_32") (pintype "bidirectional"))
    )
    (net (code "80") (name "unconnected-(IC25-EESK-Pad1)") (class "Default")
      (node (ref "IC25") (pin "1") (pinfunction "EESK_1") (pintype "bidirectional"))
    )
    (net (code "81") (name "unconnected-(IC25-PWREN#-Pad15)") (class "Default")
      (node (ref "IC25") (pin "15") (pinfunction "PWREN#_15") (pintype "bidirectional"))
    )
    (net (code "82") (name "unconnected-(IC25-RI#-Pad18)") (class "Default")
      (node (ref "IC25") (pin "18") (pinfunction "RI#_18") (pintype "bidirectional"))
    )
    (net (code "83") (name "unconnected-(IC25-RTS#-Pad23)") (class "Default")
      (node (ref "IC25") (pin "23") (pinfunction "RTS#_23") (pintype "bidirectional"))
    )
    (net (code "84") (name "unconnected-(IC25-RXLED#-Pad11)") (class "Default")
      (node (ref "IC25") (pin "11") (pinfunction "RXLED#_11") (pintype "bidirectional"))
    )
    (net (code "85") (name "unconnected-(IC25-SLEEP#-Pad10)") (class "Default")
      (node (ref "IC25") (pin "10") (pinfunction "SLEEP#_10") (pintype "bidirectional"))
    )
    (net (code "86") (name "unconnected-(IC25-TXDEN-Pad16)") (class "Default")
      (node (ref "IC25") (pin "16") (pinfunction "TXDEN_16") (pintype "bidirectional"))
    )
    (net (code "87") (name "unconnected-(IC25-TXLED#-Pad12)") (class "Default")
      (node (ref "IC25") (pin "12") (pinfunction "TXLED#_12") (pintype "bidirectional"))
    )
    (net (code "88") (name "unconnected-(MIXIN-PadR)") (class "Default")
      (node (ref "MIXIN") (pin "R") (pinfunction "R_R") (pintype "input"))
    )
    (net (code "89") (name "unconnected-(MIXIN-PadRN)") (class "Default")
      (node (ref "MIXIN") (pin "RN") (pinfunction "RN_RN") (pintype "passive"))
    )
    (net (code "90") (name "unconnected-(MIXIN-PadSN)") (class "Default")
      (node (ref "MIXIN") (pin "SN") (pinfunction "SN_SN") (pintype "passive"))
    )
    (net (code "91") (name "unconnected-(MIXOUT-PadR)") (class "Default")
      (node (ref "MIXOUT") (pin "R") (pinfunction "R_R") (pintype "input"))
    )
    (net (code "92") (name "unconnected-(MIXOUT-PadRN)") (class "Default")
      (node (ref "MIXOUT") (pin "RN") (pinfunction "RN_RN") (pintype "passive"))
    )
    (net (code "93") (name "unconnected-(MIXOUT-PadSN)") (class "Default")
      (node (ref "MIXOUT") (pin "SN") (pinfunction "SN_SN") (pintype "passive"))
    )
    (net (code "94") (name "unconnected-(MIXOUT-PadTN)") (class "Default")
      (node (ref "MIXOUT") (pin "TN") (pinfunction "TN_TN") (pintype "passive"))
    )
    (net (code "95") (name "unconnected-(POWER-PadP$3)") (class "Default")
      (node (ref "POWER") (pin "P$3") (pinfunction "P$3_P$3") (pintype "bidirectional"))
    )
  )
)
